# nucleo_board.net
KiCad netlist of a schematic drawn in EAGLE
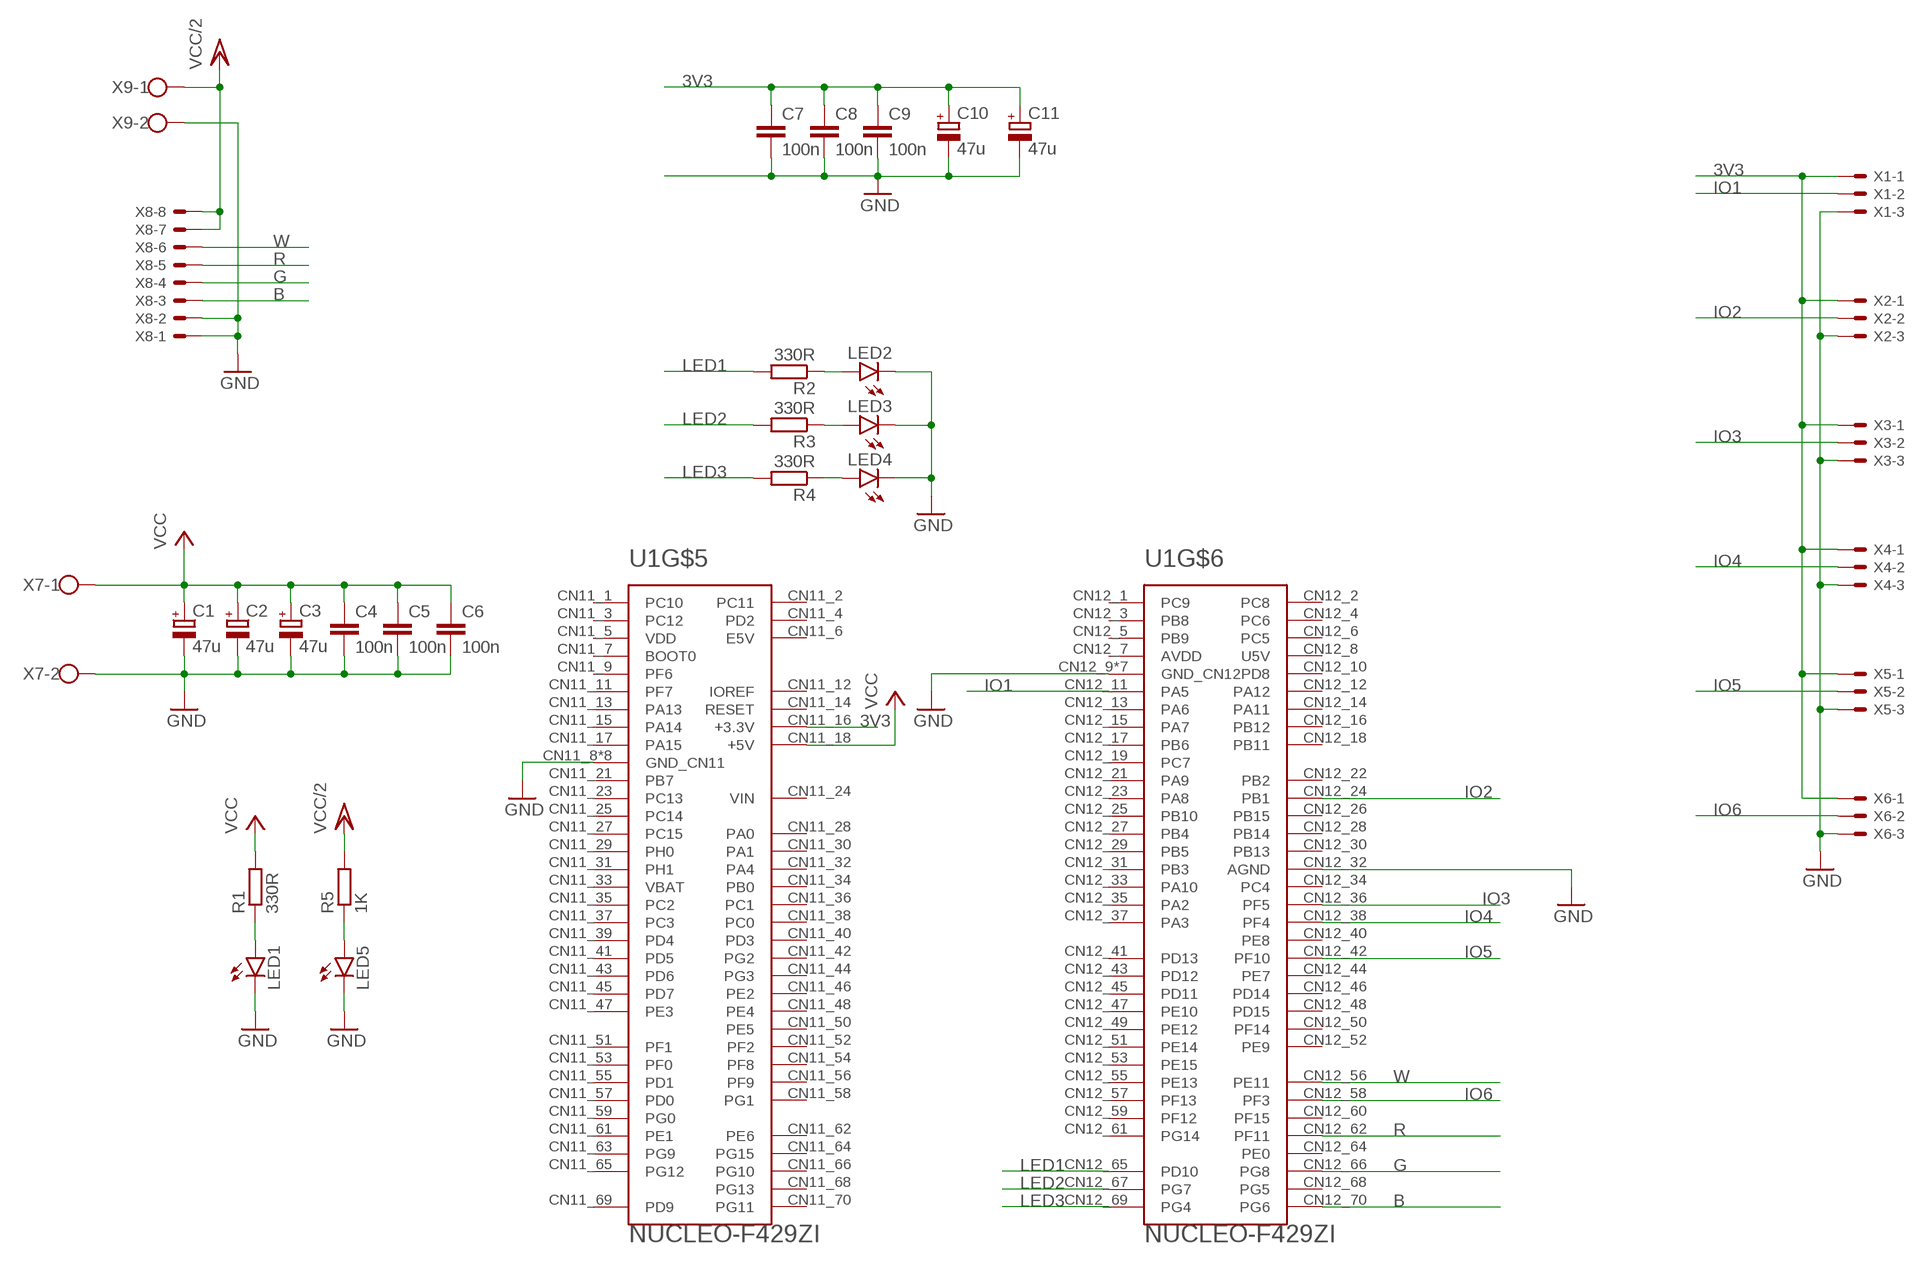
[diagram p0: schematic, sheet 1]

(export (version "E")
  (design (tool "Eeschema 10.0.6"))
  (components
    (comp (ref "C1")
      (value "47u")
      (footprint "eagle-import:153CLV-1010")
      (libsource (lib "eagle-import") (part "CPOL-EU153CLV-1010"))
    )
    (comp (ref "C2")
      (value "47u")
      (footprint "eagle-import:153CLV-1010")
      (libsource (lib "eagle-import") (part "CPOL-EU153CLV-1010"))
    )
    (comp (ref "C3")
      (value "47u")
      (footprint "eagle-import:153CLV-1010")
      (libsource (lib "eagle-import") (part "CPOL-EU153CLV-1010"))
    )
    (comp (ref "C4")
      (value "100n")
      (footprint "eagle-import:C1206")
      (libsource (lib "eagle-import") (part "C-EUC1206"))
    )
    (comp (ref "C5")
      (value "100n")
      (footprint "eagle-import:C1206")
      (libsource (lib "eagle-import") (part "C-EUC1206"))
    )
    (comp (ref "C6")
      (value "100n")
      (footprint "eagle-import:C1206")
      (libsource (lib "eagle-import") (part "C-EUC1206"))
    )
    (comp (ref "C7")
      (value "100n")
      (footprint "eagle-import:C1206")
      (libsource (lib "eagle-import") (part "C-EUC1206"))
    )
    (comp (ref "C8")
      (value "100n")
      (footprint "eagle-import:C1206")
      (libsource (lib "eagle-import") (part "C-EUC1206"))
    )
    (comp (ref "C9")
      (value "100n")
      (footprint "eagle-import:C1206")
      (libsource (lib "eagle-import") (part "C-EUC1206"))
    )
    (comp (ref "C10")
      (value "47u")
      (footprint "eagle-import:153CLV-1010")
      (libsource (lib "eagle-import") (part "CPOL-EU153CLV-1010"))
    )
    (comp (ref "C11")
      (value "47u")
      (footprint "eagle-import:153CLV-1010")
      (libsource (lib "eagle-import") (part "CPOL-EU153CLV-1010"))
    )
    (comp (ref "LED1")
      (value "LEDCHIPLED_1206")
      (footprint "eagle-import:CHIPLED_1206")
      (libsource (lib "eagle-import") (part "LEDCHIPLED_1206"))
    )
    (comp (ref "LED2")
      (value "LEDCHIPLED_1206")
      (footprint "eagle-import:CHIPLED_1206")
      (libsource (lib "eagle-import") (part "LEDCHIPLED_1206"))
    )
    (comp (ref "LED3")
      (value "LEDCHIPLED_1206")
      (footprint "eagle-import:CHIPLED_1206")
      (libsource (lib "eagle-import") (part "LEDCHIPLED_1206"))
    )
    (comp (ref "LED4")
      (value "LEDCHIPLED_1206")
      (footprint "eagle-import:CHIPLED_1206")
      (libsource (lib "eagle-import") (part "LEDCHIPLED_1206"))
    )
    (comp (ref "LED5")
      (value "LEDCHIPLED_1206")
      (footprint "eagle-import:CHIPLED_1206")
      (libsource (lib "eagle-import") (part "LEDCHIPLED_1206"))
    )
    (comp (ref "R1")
      (value "330R")
      (footprint "eagle-import:M1206")
      (libsource (lib "eagle-import") (part "R-EU_M1206"))
    )
    (comp (ref "R2")
      (value "330R")
      (footprint "eagle-import:M1206")
      (libsource (lib "eagle-import") (part "R-EU_M1206"))
    )
    (comp (ref "R3")
      (value "330R")
      (footprint "eagle-import:M1206")
      (libsource (lib "eagle-import") (part "R-EU_M1206"))
    )
    (comp (ref "R4")
      (value "330R")
      (footprint "eagle-import:M1206")
      (libsource (lib "eagle-import") (part "R-EU_M1206"))
    )
    (comp (ref "R5")
      (value "1K")
      (footprint "eagle-import:M1206")
      (libsource (lib "eagle-import") (part "R-EU_M1206"))
    )
    (comp (ref "U1")
      (value "NUCLEO-F429ZI")
      (footprint "eagle-import:MODULE_NUCLEO-F429ZI")
      (fields (field (name "DIGI-KEY_PART_NUMBER") "497-16280-ND") (field (name "MF") "STMicroelectronics"))
      (libsource (lib "eagle-import") (part "NUCLEO-F429ZI"))
    )
    (comp (ref "X1")
      (value "KK-156-3")
      (footprint "eagle-import:KK-156-3")
      (fields (field (name "MF") "MOLEX"))
      (libsource (lib "eagle-import") (part "KK-156-3"))
    )
    (comp (ref "X2")
      (value "KK-156-3")
      (footprint "eagle-import:KK-156-3")
      (fields (field (name "MF") "MOLEX"))
      (libsource (lib "eagle-import") (part "KK-156-3"))
    )
    (comp (ref "X3")
      (value "KK-156-3")
      (footprint "eagle-import:KK-156-3")
      (fields (field (name "MF") "MOLEX"))
      (libsource (lib "eagle-import") (part "KK-156-3"))
    )
    (comp (ref "X4")
      (value "KK-156-3")
      (footprint "eagle-import:KK-156-3")
      (fields (field (name "MF") "MOLEX"))
      (libsource (lib "eagle-import") (part "KK-156-3"))
    )
    (comp (ref "X5")
      (value "KK-156-3")
      (footprint "eagle-import:KK-156-3")
      (fields (field (name "MF") "MOLEX"))
      (libsource (lib "eagle-import") (part "KK-156-3"))
    )
    (comp (ref "X6")
      (value "KK-156-3")
      (footprint "eagle-import:KK-156-3")
      (fields (field (name "MF") "MOLEX"))
      (libsource (lib "eagle-import") (part "KK-156-3"))
    )
    (comp (ref "X7")
      (value "W237-102")
      (footprint "eagle-import:W237-102")
      (fields (field (name "MPN") "237-102"))
      (libsource (lib "eagle-import") (part "W237-102"))
    )
    (comp (ref "X8")
      (value "KK-156-8")
      (footprint "eagle-import:KK-156-8")
      (fields (field (name "MF") "MOLEX"))
      (libsource (lib "eagle-import") (part "KK-156-8"))
    )
    (comp (ref "X9")
      (value "W237-102")
      (footprint "eagle-import:W237-102")
      (fields (field (name "MPN") "237-102"))
      (libsource (lib "eagle-import") (part "W237-102"))
    )
  )
  (nets
    (net (code "1") (name "/3V3") (class "Default")
      (node (ref "C10") (pin "+") (pinfunction "+_+") (pintype "passive"))
      (node (ref "C11") (pin "+") (pinfunction "+_+") (pintype "passive"))
      (node (ref "C7") (pin "1") (pinfunction "1_1") (pintype "passive"))
      (node (ref "C8") (pin "1") (pinfunction "1_1") (pintype "passive"))
      (node (ref "C9") (pin "1") (pinfunction "1_1") (pintype "passive"))
      (node (ref "U1") (pin "CN11_16") (pinfunction "+3.3V_CN11_16") (pintype "passive"))
      (node (ref "X1") (pin "1") (pinfunction "S_1") (pintype "passive"))
      (node (ref "X2") (pin "1") (pinfunction "S_1") (pintype "passive"))
      (node (ref "X3") (pin "1") (pinfunction "S_1") (pintype "passive"))
      (node (ref "X4") (pin "1") (pinfunction "S_1") (pintype "passive"))
      (node (ref "X5") (pin "1") (pinfunction "S_1") (pintype "passive"))
      (node (ref "X6") (pin "1") (pinfunction "S_1") (pintype "passive"))
    )
    (net (code "2") (name "/B") (class "Default")
      (node (ref "U1") (pin "CN12_70") (pinfunction "PG6_CN12_70") (pintype "passive"))
      (node (ref "X8") (pin "3") (pinfunction "S_3") (pintype "passive"))
    )
    (net (code "3") (name "/G") (class "Default")
      (node (ref "U1") (pin "CN12_66") (pinfunction "PG8_CN12_66") (pintype "passive"))
      (node (ref "X8") (pin "4") (pinfunction "S_4") (pintype "passive"))
    )
    (net (code "4") (name "/IO1") (class "Default")
      (node (ref "U1") (pin "CN12_11") (pinfunction "PA5_CN12_11") (pintype "passive"))
      (node (ref "X1") (pin "2") (pinfunction "S_2") (pintype "passive"))
    )
    (net (code "5") (name "/IO2") (class "Default")
      (node (ref "U1") (pin "CN12_24") (pinfunction "PB1_CN12_24") (pintype "passive"))
      (node (ref "X2") (pin "2") (pinfunction "S_2") (pintype "passive"))
    )
    (net (code "6") (name "/IO3") (class "Default")
      (node (ref "U1") (pin "CN12_36") (pinfunction "PF5_CN12_36") (pintype "passive"))
      (node (ref "X3") (pin "2") (pinfunction "S_2") (pintype "passive"))
    )
    (net (code "7") (name "/IO4") (class "Default")
      (node (ref "U1") (pin "CN12_38") (pinfunction "PF4_CN12_38") (pintype "passive"))
      (node (ref "X4") (pin "2") (pinfunction "S_2") (pintype "passive"))
    )
    (net (code "8") (name "/IO5") (class "Default")
      (node (ref "U1") (pin "CN12_42") (pinfunction "PF10_CN12_42") (pintype "passive"))
      (node (ref "X5") (pin "2") (pinfunction "S_2") (pintype "passive"))
    )
    (net (code "9") (name "/IO6") (class "Default")
      (node (ref "U1") (pin "CN12_58") (pinfunction "PF3_CN12_58") (pintype "passive"))
      (node (ref "X6") (pin "2") (pinfunction "S_2") (pintype "passive"))
    )
    (net (code "10") (name "/LED1") (class "Default")
      (node (ref "R2") (pin "2") (pinfunction "2_2") (pintype "passive"))
      (node (ref "U1") (pin "CN12_65") (pinfunction "PD10_CN12_65") (pintype "passive"))
    )
    (net (code "11") (name "/LED2") (class "Default")
      (node (ref "R3") (pin "2") (pinfunction "2_2") (pintype "passive"))
      (node (ref "U1") (pin "CN12_67") (pinfunction "PG7_CN12_67") (pintype "passive"))
    )
    (net (code "12") (name "/LED3") (class "Default")
      (node (ref "R4") (pin "2") (pinfunction "2_2") (pintype "passive"))
      (node (ref "U1") (pin "CN12_69") (pinfunction "PG4_CN12_69") (pintype "passive"))
    )
    (net (code "13") (name "/R") (class "Default")
      (node (ref "U1") (pin "CN12_62") (pinfunction "PF11_CN12_62") (pintype "passive"))
      (node (ref "X8") (pin "5") (pinfunction "S_5") (pintype "passive"))
    )
    (net (code "14") (name "/W") (class "Default")
      (node (ref "U1") (pin "CN12_56") (pinfunction "PE11_CN12_56") (pintype "passive"))
      (node (ref "X8") (pin "6") (pinfunction "S_6") (pintype "passive"))
    )
    (net (code "15") (name "GND") (class "Default")
      (node (ref "C1") (pin "-") (pinfunction "-_-") (pintype "passive"))
      (node (ref "C10") (pin "-") (pinfunction "-_-") (pintype "passive"))
      (node (ref "C11") (pin "-") (pinfunction "-_-") (pintype "passive"))
      (node (ref "C2") (pin "-") (pinfunction "-_-") (pintype "passive"))
      (node (ref "C3") (pin "-") (pinfunction "-_-") (pintype "passive"))
      (node (ref "C4") (pin "2") (pinfunction "2_2") (pintype "passive"))
      (node (ref "C5") (pin "2") (pinfunction "2_2") (pintype "passive"))
      (node (ref "C6") (pin "2") (pinfunction "2_2") (pintype "passive"))
      (node (ref "C7") (pin "2") (pinfunction "2_2") (pintype "passive"))
      (node (ref "C8") (pin "2") (pinfunction "2_2") (pintype "passive"))
      (node (ref "C9") (pin "2") (pinfunction "2_2") (pintype "passive"))
      (node (ref "LED1") (pin "C") (pinfunction "C_C") (pintype "passive"))
      (node (ref "LED2") (pin "C") (pinfunction "C_C") (pintype "passive"))
      (node (ref "LED3") (pin "C") (pinfunction "C_C") (pintype "passive"))
      (node (ref "LED4") (pin "C") (pinfunction "C_C") (pintype "passive"))
      (node (ref "LED5") (pin "C") (pinfunction "C_C") (pintype "passive"))
      (node (ref "U1") (pin "CN11_19") (pinfunction "GND_CN11_CN11_19") (pintype "passive"))
      (node (ref "U1") (pin "CN11_20") (pinfunction "GND_CN11_CN11_20") (pintype "passive"))
      (node (ref "U1") (pin "CN11_22") (pinfunction "GND_CN11_CN11_22") (pintype "passive"))
      (node (ref "U1") (pin "CN11_49") (pinfunction "GND_CN11_CN11_49") (pintype "passive"))
      (node (ref "U1") (pin "CN11_60") (pinfunction "GND_CN11_CN11_60") (pintype "passive"))
      (node (ref "U1") (pin "CN11_71") (pinfunction "GND_CN11_CN11_71") (pintype "passive"))
      (node (ref "U1") (pin "CN11_72") (pinfunction "GND_CN11_CN11_72") (pintype "passive"))
      (node (ref "U1") (pin "CN11_8") (pinfunction "GND_CN11_CN11_8") (pintype "passive"))
      (node (ref "U1") (pin "CN12_20") (pinfunction "GND_CN12_CN12_20") (pintype "passive"))
      (node (ref "U1") (pin "CN12_32") (pinfunction "AGND_CN12_32") (pintype "passive"))
      (node (ref "U1") (pin "CN12_39") (pinfunction "GND_CN12_CN12_39") (pintype "passive"))
      (node (ref "U1") (pin "CN12_54") (pinfunction "GND_CN12_CN12_54") (pintype "passive"))
      (node (ref "U1") (pin "CN12_63") (pinfunction "GND_CN12_CN12_63") (pintype "passive"))
      (node (ref "U1") (pin "CN12_71") (pinfunction "GND_CN12_CN12_71") (pintype "passive"))
      (node (ref "U1") (pin "CN12_72") (pinfunction "GND_CN12_CN12_72") (pintype "passive"))
      (node (ref "U1") (pin "CN12_9") (pinfunction "GND_CN12_CN12_9") (pintype "passive"))
      (node (ref "X1") (pin "3") (pinfunction "S_3") (pintype "passive"))
      (node (ref "X2") (pin "3") (pinfunction "S_3") (pintype "passive"))
      (node (ref "X3") (pin "3") (pinfunction "S_3") (pintype "passive"))
      (node (ref "X4") (pin "3") (pinfunction "S_3") (pintype "passive"))
      (node (ref "X5") (pin "3") (pinfunction "S_3") (pintype "passive"))
      (node (ref "X6") (pin "3") (pinfunction "S_3") (pintype "passive"))
      (node (ref "X7") (pin "2") (pinfunction "KL_2") (pintype "passive"))
      (node (ref "X8") (pin "1") (pinfunction "S_1") (pintype "passive"))
      (node (ref "X8") (pin "2") (pinfunction "S_2") (pintype "passive"))
      (node (ref "X9") (pin "2") (pinfunction "KL_2") (pintype "passive"))
    )
    (net (code "16") (name "Net-(LED1-PadA)") (class "Default")
      (node (ref "LED1") (pin "A") (pinfunction "A_A") (pintype "passive"))
      (node (ref "R1") (pin "1") (pinfunction "1_1") (pintype "passive"))
    )
    (net (code "17") (name "Net-(LED2-PadA)") (class "Default")
      (node (ref "LED2") (pin "A") (pinfunction "A_A") (pintype "passive"))
      (node (ref "R2") (pin "1") (pinfunction "1_1") (pintype "passive"))
    )
    (net (code "18") (name "Net-(LED3-PadA)") (class "Default")
      (node (ref "LED3") (pin "A") (pinfunction "A_A") (pintype "passive"))
      (node (ref "R3") (pin "1") (pinfunction "1_1") (pintype "passive"))
    )
    (net (code "19") (name "Net-(LED4-PadA)") (class "Default")
      (node (ref "LED4") (pin "A") (pinfunction "A_A") (pintype "passive"))
      (node (ref "R4") (pin "1") (pinfunction "1_1") (pintype "passive"))
    )
    (net (code "20") (name "Net-(LED5-PadA)") (class "Default")
      (node (ref "LED5") (pin "A") (pinfunction "A_A") (pintype "passive"))
      (node (ref "R5") (pin "1") (pinfunction "1_1") (pintype "passive"))
    )
    (net (code "21") (name "VCC") (class "Default")
      (node (ref "C1") (pin "+") (pinfunction "+_+") (pintype "passive"))
      (node (ref "C2") (pin "+") (pinfunction "+_+") (pintype "passive"))
      (node (ref "C3") (pin "+") (pinfunction "+_+") (pintype "passive"))
      (node (ref "C4") (pin "1") (pinfunction "1_1") (pintype "passive"))
      (node (ref "C5") (pin "1") (pinfunction "1_1") (pintype "passive"))
      (node (ref "C6") (pin "1") (pinfunction "1_1") (pintype "passive"))
      (node (ref "R1") (pin "2") (pinfunction "2_2") (pintype "passive"))
      (node (ref "U1") (pin "CN11_18") (pinfunction "+5V_CN11_18") (pintype "passive"))
      (node (ref "X7") (pin "1") (pinfunction "KL_1") (pintype "passive"))
    )
    (net (code "22") (name "VCC{slash}2") (class "Default")
      (node (ref "R5") (pin "2") (pinfunction "2_2") (pintype "passive"))
      (node (ref "X8") (pin "7") (pinfunction "S_7") (pintype "passive"))
      (node (ref "X8") (pin "8") (pinfunction "S_8") (pintype "passive"))
      (node (ref "X9") (pin "1") (pinfunction "KL_1") (pintype "passive"))
    )
    (net (code "23") (name "unconnected-(U1E-BOOT0-PadCN11_7)") (class "Default")
      (node (ref "U1") (pin "CN11_7") (pinfunction "BOOT0_CN11_7") (pintype "passive"))
    )
    (net (code "24") (name "unconnected-(U1E-E5V-PadCN11_6)") (class "Default")
      (node (ref "U1") (pin "CN11_6") (pinfunction "E5V_CN11_6") (pintype "passive"))
    )
    (net (code "25") (name "unconnected-(U1E-IOREF-PadCN11_12)") (class "Default")
      (node (ref "U1") (pin "CN11_12") (pinfunction "IOREF_CN11_12") (pintype "passive"))
    )
    (net (code "26") (name "unconnected-(U1E-PA0-PadCN11_28)") (class "Default")
      (node (ref "U1") (pin "CN11_28") (pinfunction "PA0_CN11_28") (pintype "passive"))
    )
    (net (code "27") (name "unconnected-(U1E-PA1-PadCN11_30)") (class "Default")
      (node (ref "U1") (pin "CN11_30") (pinfunction "PA1_CN11_30") (pintype "passive"))
    )
    (net (code "28") (name "unconnected-(U1E-PA4-PadCN11_32)") (class "Default")
      (node (ref "U1") (pin "CN11_32") (pinfunction "PA4_CN11_32") (pintype "passive"))
    )
    (net (code "29") (name "unconnected-(U1E-PA13-PadCN11_13)") (class "Default")
      (node (ref "U1") (pin "CN11_13") (pinfunction "PA13_CN11_13") (pintype "passive"))
    )
    (net (code "30") (name "unconnected-(U1E-PA14-PadCN11_15)") (class "Default")
      (node (ref "U1") (pin "CN11_15") (pinfunction "PA14_CN11_15") (pintype "passive"))
    )
    (net (code "31") (name "unconnected-(U1E-PA15-PadCN11_17)") (class "Default")
      (node (ref "U1") (pin "CN11_17") (pinfunction "PA15_CN11_17") (pintype "passive"))
    )
    (net (code "32") (name "unconnected-(U1E-PB0-PadCN11_34)") (class "Default")
      (node (ref "U1") (pin "CN11_34") (pinfunction "PB0_CN11_34") (pintype "passive"))
    )
    (net (code "33") (name "unconnected-(U1E-PB7-PadCN11_21)") (class "Default")
      (node (ref "U1") (pin "CN11_21") (pinfunction "PB7_CN11_21") (pintype "passive"))
    )
    (net (code "34") (name "unconnected-(U1E-PC0-PadCN11_38)") (class "Default")
      (node (ref "U1") (pin "CN11_38") (pinfunction "PC0_CN11_38") (pintype "passive"))
    )
    (net (code "35") (name "unconnected-(U1E-PC1-PadCN11_36)") (class "Default")
      (node (ref "U1") (pin "CN11_36") (pinfunction "PC1_CN11_36") (pintype "passive"))
    )
    (net (code "36") (name "unconnected-(U1E-PC2-PadCN11_35)") (class "Default")
      (node (ref "U1") (pin "CN11_35") (pinfunction "PC2_CN11_35") (pintype "passive"))
    )
    (net (code "37") (name "unconnected-(U1E-PC3-PadCN11_37)") (class "Default")
      (node (ref "U1") (pin "CN11_37") (pinfunction "PC3_CN11_37") (pintype "passive"))
    )
    (net (code "38") (name "unconnected-(U1E-PC10-PadCN11_1)") (class "Default")
      (node (ref "U1") (pin "CN11_1") (pinfunction "PC10_CN11_1") (pintype "passive"))
    )
    (net (code "39") (name "unconnected-(U1E-PC11-PadCN11_2)") (class "Default")
      (node (ref "U1") (pin "CN11_2") (pinfunction "PC11_CN11_2") (pintype "passive"))
    )
    (net (code "40") (name "unconnected-(U1E-PC12-PadCN11_3)") (class "Default")
      (node (ref "U1") (pin "CN11_3") (pinfunction "PC12_CN11_3") (pintype "passive"))
    )
    (net (code "41") (name "unconnected-(U1E-PC13-PadCN11_23)") (class "Default")
      (node (ref "U1") (pin "CN11_23") (pinfunction "PC13_CN11_23") (pintype "passive"))
    )
    (net (code "42") (name "unconnected-(U1E-PC14-PadCN11_25)") (class "Default")
      (node (ref "U1") (pin "CN11_25") (pinfunction "PC14_CN11_25") (pintype "passive"))
    )
    (net (code "43") (name "unconnected-(U1E-PC15-PadCN11_27)") (class "Default")
      (node (ref "U1") (pin "CN11_27") (pinfunction "PC15_CN11_27") (pintype "passive"))
    )
    (net (code "44") (name "unconnected-(U1E-PD0-PadCN11_57)") (class "Default")
      (node (ref "U1") (pin "CN11_57") (pinfunction "PD0_CN11_57") (pintype "passive"))
    )
    (net (code "45") (name "unconnected-(U1E-PD1-PadCN11_55)") (class "Default")
      (node (ref "U1") (pin "CN11_55") (pinfunction "PD1_CN11_55") (pintype "passive"))
    )
    (net (code "46") (name "unconnected-(U1E-PD2-PadCN11_4)") (class "Default")
      (node (ref "U1") (pin "CN11_4") (pinfunction "PD2_CN11_4") (pintype "passive"))
    )
    (net (code "47") (name "unconnected-(U1E-PD3-PadCN11_40)") (class "Default")
      (node (ref "U1") (pin "CN11_40") (pinfunction "PD3_CN11_40") (pintype "passive"))
    )
    (net (code "48") (name "unconnected-(U1E-PD4-PadCN11_39)") (class "Default")
      (node (ref "U1") (pin "CN11_39") (pinfunction "PD4_CN11_39") (pintype "passive"))
    )
    (net (code "49") (name "unconnected-(U1E-PD5-PadCN11_41)") (class "Default")
      (node (ref "U1") (pin "CN11_41") (pinfunction "PD5_CN11_41") (pintype "passive"))
    )
    (net (code "50") (name "unconnected-(U1E-PD6-PadCN11_43)") (class "Default")
      (node (ref "U1") (pin "CN11_43") (pinfunction "PD6_CN11_43") (pintype "passive"))
    )
    (net (code "51") (name "unconnected-(U1E-PD7-PadCN11_45)") (class "Default")
      (node (ref "U1") (pin "CN11_45") (pinfunction "PD7_CN11_45") (pintype "passive"))
    )
    (net (code "52") (name "unconnected-(U1E-PD9-PadCN11_69)") (class "Default")
      (node (ref "U1") (pin "CN11_69") (pinfunction "PD9_CN11_69") (pintype "passive"))
    )
    (net (code "53") (name "unconnected-(U1E-PE1-PadCN11_61)") (class "Default")
      (node (ref "U1") (pin "CN11_61") (pinfunction "PE1_CN11_61") (pintype "passive"))
    )
    (net (code "54") (name "unconnected-(U1E-PE2-PadCN11_46)") (class "Default")
      (node (ref "U1") (pin "CN11_46") (pinfunction "PE2_CN11_46") (pintype "passive"))
    )
    (net (code "55") (name "unconnected-(U1E-PE3-PadCN11_47)") (class "Default")
      (node (ref "U1") (pin "CN11_47") (pinfunction "PE3_CN11_47") (pintype "passive"))
    )
    (net (code "56") (name "unconnected-(U1E-PE4-PadCN11_48)") (class "Default")
      (node (ref "U1") (pin "CN11_48") (pinfunction "PE4_CN11_48") (pintype "passive"))
    )
    (net (code "57") (name "unconnected-(U1E-PE5-PadCN11_50)") (class "Default")
      (node (ref "U1") (pin "CN11_50") (pinfunction "PE5_CN11_50") (pintype "passive"))
    )
    (net (code "58") (name "unconnected-(U1E-PE6-PadCN11_62)") (class "Default")
      (node (ref "U1") (pin "CN11_62") (pinfunction "PE6_CN11_62") (pintype "passive"))
    )
    (net (code "59") (name "unconnected-(U1E-PF0-PadCN11_53)") (class "Default")
      (node (ref "U1") (pin "CN11_53") (pinfunction "PF0_CN11_53") (pintype "passive"))
    )
    (net (code "60") (name "unconnected-(U1E-PF1-PadCN11_51)") (class "Default")
      (node (ref "U1") (pin "CN11_51") (pinfunction "PF1_CN11_51") (pintype "passive"))
    )
    (net (code "61") (name "unconnected-(U1E-PF2-PadCN11_52)") (class "Default")
      (node (ref "U1") (pin "CN11_52") (pinfunction "PF2_CN11_52") (pintype "passive"))
    )
    (net (code "62") (name "unconnected-(U1E-PF6-PadCN11_9)") (class "Default")
      (node (ref "U1") (pin "CN11_9") (pinfunction "PF6_CN11_9") (pintype "passive"))
    )
    (net (code "63") (name "unconnected-(U1E-PF7-PadCN11_11)") (class "Default")
      (node (ref "U1") (pin "CN11_11") (pinfunction "PF7_CN11_11") (pintype "passive"))
    )
    (net (code "64") (name "unconnected-(U1E-PF8-PadCN11_54)") (class "Default")
      (node (ref "U1") (pin "CN11_54") (pinfunction "PF8_CN11_54") (pintype "passive"))
    )
    (net (code "65") (name "unconnected-(U1E-PF9-PadCN11_56)") (class "Default")
      (node (ref "U1") (pin "CN11_56") (pinfunction "PF9_CN11_56") (pintype "passive"))
    )
    (net (code "66") (name "unconnected-(U1E-PG0-PadCN11_59)") (class "Default")
      (node (ref "U1") (pin "CN11_59") (pinfunction "PG0_CN11_59") (pintype "passive"))
    )
    (net (code "67") (name "unconnected-(U1E-PG1-PadCN11_58)") (class "Default")
      (node (ref "U1") (pin "CN11_58") (pinfunction "PG1_CN11_58") (pintype "passive"))
    )
    (net (code "68") (name "unconnected-(U1E-PG2-PadCN11_42)") (class "Default")
      (node (ref "U1") (pin "CN11_42") (pinfunction "PG2_CN11_42") (pintype "passive"))
    )
    (net (code "69") (name "unconnected-(U1E-PG3-PadCN11_44)") (class "Default")
      (node (ref "U1") (pin "CN11_44") (pinfunction "PG3_CN11_44") (pintype "passive"))
    )
    (net (code "70") (name "unconnected-(U1E-PG9-PadCN11_63)") (class "Default")
      (node (ref "U1") (pin "CN11_63") (pinfunction "PG9_CN11_63") (pintype "passive"))
    )
    (net (code "71") (name "unconnected-(U1E-PG10-PadCN11_66)") (class "Default")
      (node (ref "U1") (pin "CN11_66") (pinfunction "PG10_CN11_66") (pintype "passive"))
    )
    (net (code "72") (name "unconnected-(U1E-PG11-PadCN11_70)") (class "Default")
      (node (ref "U1") (pin "CN11_70") (pinfunction "PG11_CN11_70") (pintype "passive"))
    )
    (net (code "73") (name "unconnected-(U1E-PG12-PadCN11_65)") (class "Default")
      (node (ref "U1") (pin "CN11_65") (pinfunction "PG12_CN11_65") (pintype "passive"))
    )
    (net (code "74") (name "unconnected-(U1E-PG13-PadCN11_68)") (class "Default")
      (node (ref "U1") (pin "CN11_68") (pinfunction "PG13_CN11_68") (pintype "passive"))
    )
    (net (code "75") (name "unconnected-(U1E-PG15-PadCN11_64)") (class "Default")
      (node (ref "U1") (pin "CN11_64") (pinfunction "PG15_CN11_64") (pintype "passive"))
    )
    (net (code "76") (name "unconnected-(U1E-PH0-PadCN11_29)") (class "Default")
      (node (ref "U1") (pin "CN11_29") (pinfunction "PH0_CN11_29") (pintype "passive"))
    )
    (net (code "77") (name "unconnected-(U1E-PH1-PadCN11_31)") (class "Default")
      (node (ref "U1") (pin "CN11_31") (pinfunction "PH1_CN11_31") (pintype "passive"))
    )
    (net (code "78") (name "unconnected-(U1E-RESET-PadCN11_14)") (class "Default")
      (node (ref "U1") (pin "CN11_14") (pinfunction "RESET_CN11_14") (pintype "passive"))
    )
    (net (code "79") (name "unconnected-(U1E-VBAT-PadCN11_33)") (class "Default")
      (node (ref "U1") (pin "CN11_33") (pinfunction "VBAT_CN11_33") (pintype "passive"))
    )
    (net (code "80") (name "unconnected-(U1E-VDD-PadCN11_5)") (class "Default")
      (node (ref "U1") (pin "CN11_5") (pinfunction "VDD_CN11_5") (pintype "passive"))
    )
    (net (code "81") (name "unconnected-(U1E-VIN-PadCN11_24)") (class "Default")
      (node (ref "U1") (pin "CN11_24") (pinfunction "VIN_CN11_24") (pintype "passive"))
    )
    (net (code "82") (name "unconnected-(U1F-AVDD-PadCN12_7)") (class "Default")
      (node (ref "U1") (pin "CN12_7") (pinfunction "AVDD_CN12_7") (pintype "passive"))
    )
    (net (code "83") (name "unconnected-(U1F-PA2-PadCN12_35)") (class "Default")
      (node (ref "U1") (pin "CN12_35") (pinfunction "PA2_CN12_35") (pintype "passive"))
    )
    (net (code "84") (name "unconnected-(U1F-PA3-PadCN12_37)") (class "Default")
      (node (ref "U1") (pin "CN12_37") (pinfunction "PA3_CN12_37") (pintype "passive"))
    )
    (net (code "85") (name "unconnected-(U1F-PA6-PadCN12_13)") (class "Default")
      (node (ref "U1") (pin "CN12_13") (pinfunction "PA6_CN12_13") (pintype "passive"))
    )
    (net (code "86") (name "unconnected-(U1F-PA7-PadCN12_15)") (class "Default")
      (node (ref "U1") (pin "CN12_15") (pinfunction "PA7_CN12_15") (pintype "passive"))
    )
    (net (code "87") (name "unconnected-(U1F-PA8-PadCN12_23)") (class "Default")
      (node (ref "U1") (pin "CN12_23") (pinfunction "PA8_CN12_23") (pintype "passive"))
    )
    (net (code "88") (name "unconnected-(U1F-PA9-PadCN12_21)") (class "Default")
      (node (ref "U1") (pin "CN12_21") (pinfunction "PA9_CN12_21") (pintype "passive"))
    )
    (net (code "89") (name "unconnected-(U1F-PA10-PadCN12_33)") (class "Default")
      (node (ref "U1") (pin "CN12_33") (pinfunction "PA10_CN12_33") (pintype "passive"))
    )
    (net (code "90") (name "unconnected-(U1F-PA11-PadCN12_14)") (class "Default")
      (node (ref "U1") (pin "CN12_14") (pinfunction "PA11_CN12_14") (pintype "passive"))
    )
    (net (code "91") (name "unconnected-(U1F-PA12-PadCN12_12)") (class "Default")
      (node (ref "U1") (pin "CN12_12") (pinfunction "PA12_CN12_12") (pintype "passive"))
    )
    (net (code "92") (name "unconnected-(U1F-PB2-PadCN12_22)") (class "Default")
      (node (ref "U1") (pin "CN12_22") (pinfunction "PB2_CN12_22") (pintype "passive"))
    )
    (net (code "93") (name "unconnected-(U1F-PB3-PadCN12_31)") (class "Default")
      (node (ref "U1") (pin "CN12_31") (pinfunction "PB3_CN12_31") (pintype "passive"))
    )
    (net (code "94") (name "unconnected-(U1F-PB4-PadCN12_27)") (class "Default")
      (node (ref "U1") (pin "CN12_27") (pinfunction "PB4_CN12_27") (pintype "passive"))
    )
    (net (code "95") (name "unconnected-(U1F-PB5-PadCN12_29)") (class "Default")
      (node (ref "U1") (pin "CN12_29") (pinfunction "PB5_CN12_29") (pintype "passive"))
    )
    (net (code "96") (name "unconnected-(U1F-PB6-PadCN12_17)") (class "Default")
      (node (ref "U1") (pin "CN12_17") (pinfunction "PB6_CN12_17") (pintype "passive"))
    )
    (net (code "97") (name "unconnected-(U1F-PB8-PadCN12_3)") (class "Default")
      (node (ref "U1") (pin "CN12_3") (pinfunction "PB8_CN12_3") (pintype "passive"))
    )
    (net (code "98") (name "unconnected-(U1F-PB9-PadCN12_5)") (class "Default")
      (node (ref "U1") (pin "CN12_5") (pinfunction "PB9_CN12_5") (pintype "passive"))
    )
    (net (code "99") (name "unconnected-(U1F-PB10-PadCN12_25)") (class "Default")
      (node (ref "U1") (pin "CN12_25") (pinfunction "PB10_CN12_25") (pintype "passive"))
    )
    (net (code "100") (name "unconnected-(U1F-PB11-PadCN12_18)") (class "Default")
      (node (ref "U1") (pin "CN12_18") (pinfunction "PB11_CN12_18") (pintype "passive"))
    )
    (net (code "101") (name "unconnected-(U1F-PB12-PadCN12_16)") (class "Default")
      (node (ref "U1") (pin "CN12_16") (pinfunction "PB12_CN12_16") (pintype "passive"))
    )
    (net (code "102") (name "unconnected-(U1F-PB13-PadCN12_30)") (class "Default")
      (node (ref "U1") (pin "CN12_30") (pinfunction "PB13_CN12_30") (pintype "passive"))
    )
    (net (code "103") (name "unconnected-(U1F-PB14-PadCN12_28)") (class "Default")
      (node (ref "U1") (pin "CN12_28") (pinfunction "PB14_CN12_28") (pintype "passive"))
    )
    (net (code "104") (name "unconnected-(U1F-PB15-PadCN12_26)") (class "Default")
      (node (ref "U1") (pin "CN12_26") (pinfunction "PB15_CN12_26") (pintype "passive"))
    )
    (net (code "105") (name "unconnected-(U1F-PC4-PadCN12_34)") (class "Default")
      (node (ref "U1") (pin "CN12_34") (pinfunction "PC4_CN12_34") (pintype "passive"))
    )
    (net (code "106") (name "unconnected-(U1F-PC5-PadCN12_6)") (class "Default")
      (node (ref "U1") (pin "CN12_6") (pinfunction "PC5_CN12_6") (pintype "passive"))
    )
    (net (code "107") (name "unconnected-(U1F-PC6-PadCN12_4)") (class "Default")
      (node (ref "U1") (pin "CN12_4") (pinfunction "PC6_CN12_4") (pintype "passive"))
    )
    (net (code "108") (name "unconnected-(U1F-PC7-PadCN12_19)") (class "Default")
      (node (ref "U1") (pin "CN12_19") (pinfunction "PC7_CN12_19") (pintype "passive"))
    )
    (net (code "109") (name "unconnected-(U1F-PC8-PadCN12_2)") (class "Default")
      (node (ref "U1") (pin "CN12_2") (pinfunction "PC8_CN12_2") (pintype "passive"))
    )
    (net (code "110") (name "unconnected-(U1F-PC9-PadCN12_1)") (class "Default")
      (node (ref "U1") (pin "CN12_1") (pinfunction "PC9_CN12_1") (pintype "passive"))
    )
    (net (code "111") (name "unconnected-(U1F-PD8-PadCN12_10)") (class "Default")
      (node (ref "U1") (pin "CN12_10") (pinfunction "PD8_CN12_10") (pintype "passive"))
    )
    (net (code "112") (name "unconnected-(U1F-PD11-PadCN12_45)") (class "Default")
      (node (ref "U1") (pin "CN12_45") (pinfunction "PD11_CN12_45") (pintype "passive"))
    )
    (net (code "113") (name "unconnected-(U1F-PD12-PadCN12_43)") (class "Default")
      (node (ref "U1") (pin "CN12_43") (pinfunction "PD12_CN12_43") (pintype "passive"))
    )
    (net (code "114") (name "unconnected-(U1F-PD13-PadCN12_41)") (class "Default")
      (node (ref "U1") (pin "CN12_41") (pinfunction "PD13_CN12_41") (pintype "passive"))
    )
    (net (code "115") (name "unconnected-(U1F-PD14-PadCN12_46)") (class "Default")
      (node (ref "U1") (pin "CN12_46") (pinfunction "PD14_CN12_46") (pintype "passive"))
    )
    (net (code "116") (name "unconnected-(U1F-PD15-PadCN12_48)") (class "Default")
      (node (ref "U1") (pin "CN12_48") (pinfunction "PD15_CN12_48") (pintype "passive"))
    )
    (net (code "117") (name "unconnected-(U1F-PE0-PadCN12_64)") (class "Default")
      (node (ref "U1") (pin "CN12_64") (pinfunction "PE0_CN12_64") (pintype "passive"))
    )
    (net (code "118") (name "unconnected-(U1F-PE7-PadCN12_44)") (class "Default")
      (node (ref "U1") (pin "CN12_44") (pinfunction "PE7_CN12_44") (pintype "passive"))
    )
    (net (code "119") (name "unconnected-(U1F-PE8-PadCN12_40)") (class "Default")
      (node (ref "U1") (pin "CN12_40") (pinfunction "PE8_CN12_40") (pintype "passive"))
    )
    (net (code "120") (name "unconnected-(U1F-PE9-PadCN12_52)") (class "Default")
      (node (ref "U1") (pin "CN12_52") (pinfunction "PE9_CN12_52") (pintype "passive"))
    )
    (net (code "121") (name "unconnected-(U1F-PE10-PadCN12_47)") (class "Default")
      (node (ref "U1") (pin "CN12_47") (pinfunction "PE10_CN12_47") (pintype "passive"))
    )
    (net (code "122") (name "unconnected-(U1F-PE12-PadCN12_49)") (class "Default")
      (node (ref "U1") (pin "CN12_49") (pinfunction "PE12_CN12_49") (pintype "passive"))
    )
    (net (code "123") (name "unconnected-(U1F-PE13-PadCN12_55)") (class "Default")
      (node (ref "U1") (pin "CN12_55") (pinfunction "PE13_CN12_55") (pintype "passive"))
    )
    (net (code "124") (name "unconnected-(U1F-PE14-PadCN12_51)") (class "Default")
      (node (ref "U1") (pin "CN12_51") (pinfunction "PE14_CN12_51") (pintype "passive"))
    )
    (net (code "125") (name "unconnected-(U1F-PE15-PadCN12_53)") (class "Default")
      (node (ref "U1") (pin "CN12_53") (pinfunction "PE15_CN12_53") (pintype "passive"))
    )
    (net (code "126") (name "unconnected-(U1F-PF12-PadCN12_59)") (class "Default")
      (node (ref "U1") (pin "CN12_59") (pinfunction "PF12_CN12_59") (pintype "passive"))
    )
    (net (code "127") (name "unconnected-(U1F-PF13-PadCN12_57)") (class "Default")
      (node (ref "U1") (pin "CN12_57") (pinfunction "PF13_CN12_57") (pintype "passive"))
    )
    (net (code "128") (name "unconnected-(U1F-PF14-PadCN12_50)") (class "Default")
      (node (ref "U1") (pin "CN12_50") (pinfunction "PF14_CN12_50") (pintype "passive"))
    )
    (net (code "129") (name "unconnected-(U1F-PF15-PadCN12_60)") (class "Default")
      (node (ref "U1") (pin "CN12_60") (pinfunction "PF15_CN12_60") (pintype "passive"))
    )
    (net (code "130") (name "unconnected-(U1F-PG5-PadCN12_68)") (class "Default")
      (node (ref "U1") (pin "CN12_68") (pinfunction "PG5_CN12_68") (pintype "passive"))
    )
    (net (code "131") (name "unconnected-(U1F-PG14-PadCN12_61)") (class "Default")
      (node (ref "U1") (pin "CN12_61") (pinfunction "PG14_CN12_61") (pintype "passive"))
    )
    (net (code "132") (name "unconnected-(U1F-U5V-PadCN12_8)") (class "Default")
      (node (ref "U1") (pin "CN12_8") (pinfunction "U5V_CN12_8") (pintype "passive"))
    )
  )
)
